# OpAmpSD.net
KiCad netlist of a schematic drawn in Altium Designer
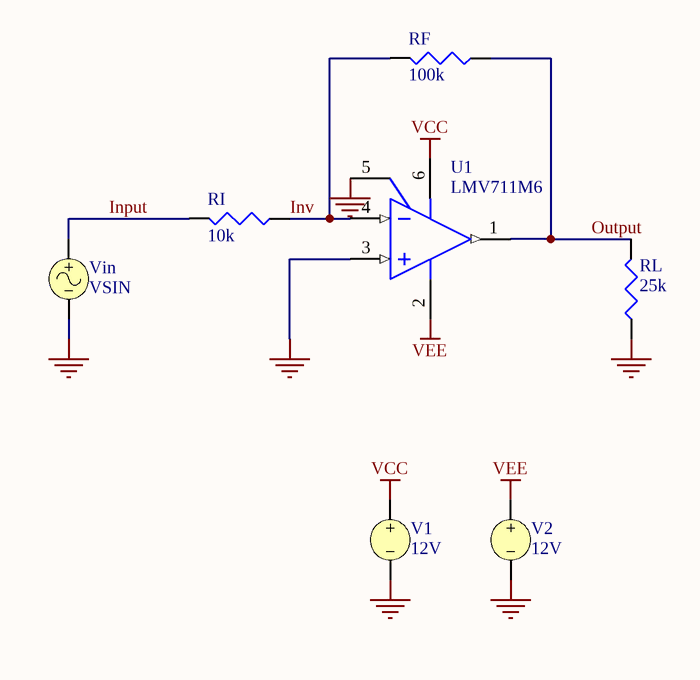
[diagram p0: OpAmpSD.schdoc]

(export (version "E")
  (design (tool "Eeschema 10.0.6"))
  (components
    (comp (ref "RF") (value "100k") (description "Resistor") (libsource (lib "*") (part "RES")))
    (comp (ref "RI") (value "10k") (description "Resistor") (libsource (lib "*") (part "RES")))
    (comp (ref "RL") (value "25k") (description "Resistor") (libsource (lib "") (part "RES_1")))
    (comp (ref "U1")
      (value "LMV711M6")
      (footprint "MF06A_N")
      (description "Low Power, RRIO Operational Amplifiers with High Output Current Drive and Shutdown Option")
      (fields
        (field (name "MANUFACTURER") "National Semiconductor")
        (field (name "DIGIKEYPARTNUMBER") "LMV711M6CT-ND")
        (field (name "PUBLISHER") "Altium Limited")
      )
      (libsource (lib "NSC Amplifier with SIM models") (part "LMV711M6"))
    )
    (comp (ref "V1") (value "12V") (description "Voltage Source") (libsource (lib "*") (part "VSRC")))
    (comp (ref "V2")
      (value "12V")
      (description "Voltage Source")
      (fields (field (name "Comment") "-12V"))
      (libsource (lib "*") (part "VSRC"))
    )
    (comp (ref "Vin")
      (value "VSIN")
      (description "Sinusoidal Voltage Source")
      (libsource (lib "*") (part "VSIN"))
    )
  )
  (nets
    (net (code "1") (name "/Input") (class "Default")
      (node (ref "RI") (pin "1") (pinfunction "TOP_1") (pintype "passive"))
      (node (ref "Vin") (pin "1") (pinfunction "1_1") (pintype "passive"))
    )
    (net (code "2") (name "/Inv") (class "Default")
      (node (ref "RF") (pin "1") (pinfunction "TOP_1") (pintype "passive"))
      (node (ref "RI") (pin "2") (pinfunction "BOT_2") (pintype "passive"))
      (node (ref "U1") (pin "4") (pinfunction "IN-_4") (pintype "input"))
    )
    (net (code "3") (name "/Output") (class "Default")
      (node (ref "RF") (pin "2") (pinfunction "BOT_2") (pintype "passive"))
      (node (ref "RL") (pin "1") (pinfunction "TOP_1") (pintype "passive"))
      (node (ref "U1") (pin "1") (pinfunction "OUT_1") (pintype "output"))
    )
    (net (code "4") (name "GND") (class "Default")
      (node (ref "RL") (pin "2") (pinfunction "BOT_2") (pintype "passive"))
      (node (ref "U1") (pin "3") (pinfunction "IN+_3") (pintype "input"))
      (node (ref "U1") (pin "5") (pinfunction "SHDN_5") (pintype "passive"))
      (node (ref "V1") (pin "2") (pinfunction "2_2") (pintype "passive"))
      (node (ref "V2") (pin "2") (pinfunction "2_2") (pintype "passive"))
      (node (ref "Vin") (pin "2") (pinfunction "2_2") (pintype "passive"))
    )
    (net (code "5") (name "VCC") (class "Default")
      (node (ref "U1") (pin "6") (pinfunction "V+_6") (pintype "power_in"))
      (node (ref "V1") (pin "1") (pinfunction "1_1") (pintype "passive"))
    )
    (net (code "6") (name "VEE") (class "Default")
      (node (ref "U1") (pin "2") (pinfunction "V-_2") (pintype "power_in"))
      (node (ref "V2") (pin "1") (pinfunction "1_1") (pintype "passive"))
    )
  )
)
